# SPI_schematic.net
KiCad netlist of a schematic drawn in EAGLE
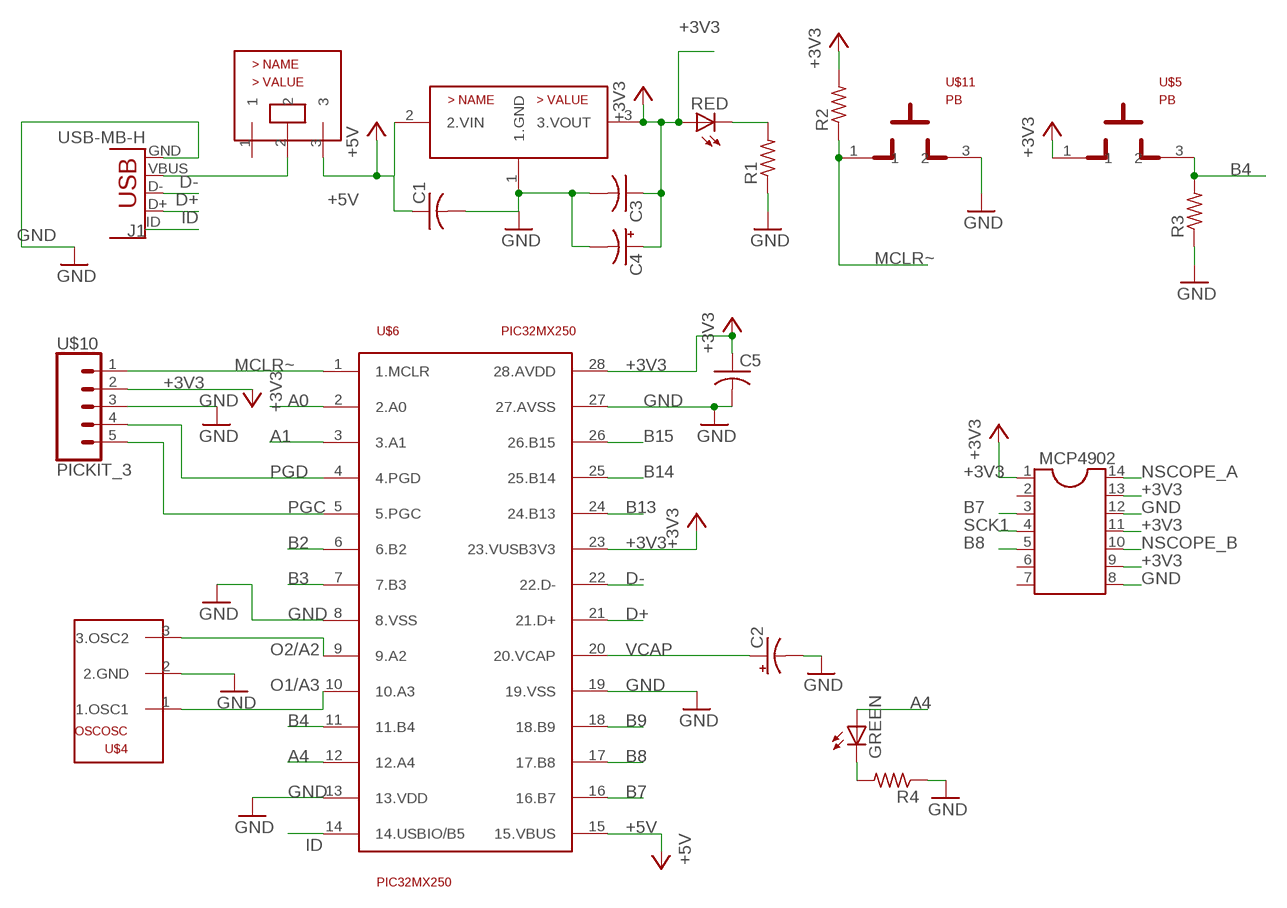
[diagram p0: schematic, sheet 1]

(export (version "E")
  (design (tool "Eeschema 10.0.6"))
  (components
    (comp (ref "C1")
      (value "C-US025-025X050")
      (footprint "eagle-import:C025-025X050")
      (libsource (lib "eagle-import") (part "C-US025-025X050"))
    )
    (comp (ref "C2")
      (value "CPOL-USB45181B")
      (footprint "eagle-import:B45181B")
      (libsource (lib "eagle-import") (part "CPOL-USB45181B"))
    )
    (comp (ref "C3")
      (value "C-US025-025X050")
      (footprint "eagle-import:C025-025X050")
      (libsource (lib "eagle-import") (part "C-US025-025X050"))
    )
    (comp (ref "C4")
      (value "CPOL-USB45181B")
      (footprint "eagle-import:B45181B")
      (libsource (lib "eagle-import") (part "CPOL-USB45181B"))
    )
    (comp (ref "C5")
      (value "C-US025-025X050")
      (footprint "eagle-import:C025-025X050")
      (libsource (lib "eagle-import") (part "C-US025-025X050"))
    )
    (comp (ref "GREEN")
      (value "LED3MM")
      (footprint "eagle-import:LED3MM")
      (libsource (lib "eagle-import") (part "LED3MM"))
    )
    (comp (ref "J1")
      (value "USB-MB-H")
      (footprint "eagle-import:USB-MB-H")
      (libsource (lib "eagle-import") (part "USB-MB-H"))
    )
    (comp (ref "MCP4902")
      (value "DIL14")
      (footprint "eagle-import:DIL14")
      (libsource (lib "eagle-import") (part "DIL14"))
    )
    (comp (ref "R1")
      (value "R-US_0204/7")
      (footprint "eagle-import:0204_7")
      (libsource (lib "eagle-import") (part "R-US_0204/7"))
    )
    (comp (ref "R2")
      (value "R-US_0204/7")
      (footprint "eagle-import:0204_7")
      (libsource (lib "eagle-import") (part "R-US_0204/7"))
    )
    (comp (ref "R3")
      (value "R-US_0204/7")
      (footprint "eagle-import:0204_7")
      (libsource (lib "eagle-import") (part "R-US_0204/7"))
    )
    (comp (ref "R4")
      (value "R-US_0204/7")
      (footprint "eagle-import:0204_7")
      (libsource (lib "eagle-import") (part "R-US_0204/7"))
    )
    (comp (ref "RED")
      (value "LED3MM")
      (footprint "eagle-import:LED3MM")
      (libsource (lib "eagle-import") (part "LED3MM"))
    )
    (comp (ref "U$4")
      (value "OSCOSC")
      (footprint "eagle-import:OSC")
      (libsource (lib "eagle-import") (part "OSCOSC"))
    )
    (comp (ref "U$5") (value "PB") (footprint "eagle-import:PB") (libsource (lib "eagle-import") (part "PB")))
    (comp (ref "U$6")
      (value "PIC32MX250")
      (footprint "eagle-import:DIL28-3")
      (libsource (lib "eagle-import") (part "PIC32MX250"))
    )
    (comp (ref "U$8")
      (value "SLIDE")
      (footprint "eagle-import:SLIDE")
      (libsource (lib "eagle-import") (part "SLIDE"))
    )
    (comp (ref "U$10")
      (value "PICKIT_3")
      (footprint "eagle-import:1X05")
      (libsource (lib "eagle-import") (part "PICKIT_3"))
    )
    (comp (ref "U$11")
      (value "PB")
      (footprint "eagle-import:PB")
      (libsource (lib "eagle-import") (part "PB"))
    )
    (comp (ref "_")
      (value "MCP1702")
      (footprint "eagle-import:TO92")
      (libsource (lib "eagle-import") (part "MCP1702"))
    )
  )
  (nets
    (net (code "1") (name "+3V3") (class "Default")
      (node (ref "C3") (pin "1") (pinfunction "1_1") (pintype "passive"))
      (node (ref "C4") (pin "+") (pinfunction "+_+") (pintype "passive"))
      (node (ref "C5") (pin "1") (pinfunction "1_1") (pintype "passive"))
      (node (ref "MCP4902") (pin "1") (pinfunction "1_1") (pintype "passive"))
      (node (ref "MCP4902") (pin "11") (pinfunction "11_11") (pintype "passive"))
      (node (ref "MCP4902") (pin "13") (pinfunction "13_13") (pintype "passive"))
      (node (ref "MCP4902") (pin "9") (pinfunction "9_9") (pintype "passive"))
      (node (ref "R2") (pin "2") (pinfunction "2_2") (pintype "passive"))
      (node (ref "RED") (pin "A") (pinfunction "A_A") (pintype "passive"))
      (node (ref "U$10") (pin "2") (pinfunction "2.VDD_2") (pintype "passive"))
      (node (ref "U$5") (pin "1") (pinfunction "1_1") (pintype "bidirectional"))
      (node (ref "U$6") (pin "23") (pinfunction "23.VUSB3V3_23") (pintype "bidirectional"))
      (node (ref "U$6") (pin "28") (pinfunction "28.AVDD_28") (pintype "bidirectional"))
      (node (ref "_") (pin "3") (pinfunction "3.VOUT_3") (pintype "bidirectional"))
    )
    (net (code "2") (name "+5V") (class "Default")
      (node (ref "C1") (pin "1") (pinfunction "1_1") (pintype "passive"))
      (node (ref "U$6") (pin "15") (pinfunction "15.VBUS_15") (pintype "bidirectional"))
      (node (ref "U$8") (pin "3") (pinfunction "3_3") (pintype "bidirectional"))
      (node (ref "_") (pin "2") (pinfunction "2.VIN_2") (pintype "bidirectional"))
    )
    (net (code "3") (name "/A0") (class "Default")
      (node (ref "U$6") (pin "2") (pinfunction "2.A0_2") (pintype "bidirectional"))
    )
    (net (code "4") (name "/A1") (class "Default")
      (node (ref "U$6") (pin "3") (pinfunction "3.A1_3") (pintype "bidirectional"))
    )
    (net (code "5") (name "/A4") (class "Default")
      (node (ref "GREEN") (pin "A") (pinfunction "A_A") (pintype "passive"))
      (node (ref "U$6") (pin "12") (pinfunction "12.A4_12") (pintype "bidirectional"))
    )
    (net (code "6") (name "/B2") (class "Default")
      (node (ref "U$6") (pin "6") (pinfunction "6.B2_6") (pintype "bidirectional"))
    )
    (net (code "7") (name "/B3") (class "Default")
      (node (ref "U$6") (pin "7") (pinfunction "7.B3_7") (pintype "bidirectional"))
    )
    (net (code "8") (name "/B4") (class "Default")
      (node (ref "R3") (pin "2") (pinfunction "2_2") (pintype "passive"))
      (node (ref "U$5") (pin "3") (pinfunction "2_3") (pintype "bidirectional"))
      (node (ref "U$6") (pin "11") (pinfunction "11.B4_11") (pintype "bidirectional"))
    )
    (net (code "9") (name "/B7") (class "Default")
      (node (ref "MCP4902") (pin "3") (pinfunction "3_3") (pintype "passive"))
      (node (ref "U$6") (pin "16") (pinfunction "16.B7_16") (pintype "bidirectional"))
    )
    (net (code "10") (name "/B8") (class "Default")
      (node (ref "MCP4902") (pin "5") (pinfunction "5_5") (pintype "passive"))
      (node (ref "U$6") (pin "17") (pinfunction "17.B8_17") (pintype "bidirectional"))
    )
    (net (code "11") (name "/B9") (class "Default")
      (node (ref "U$6") (pin "18") (pinfunction "18.B9_18") (pintype "bidirectional"))
    )
    (net (code "12") (name "/B13") (class "Default")
      (node (ref "U$6") (pin "24") (pinfunction "24.B13_24") (pintype "bidirectional"))
    )
    (net (code "13") (name "/B14") (class "Default")
      (node (ref "U$6") (pin "25") (pinfunction "25.B14_25") (pintype "bidirectional"))
    )
    (net (code "14") (name "/B15") (class "Default")
      (node (ref "U$6") (pin "26") (pinfunction "26.B15_26") (pintype "bidirectional"))
    )
    (net (code "15") (name "/D+") (class "Default")
      (node (ref "J1") (pin "D+") (pinfunction "D+_D+") (pintype "bidirectional"))
      (node (ref "U$6") (pin "21") (pinfunction "21.D+_21") (pintype "bidirectional"))
    )
    (net (code "16") (name "/D-") (class "Default")
      (node (ref "J1") (pin "D-") (pinfunction "D-_D-") (pintype "bidirectional"))
      (node (ref "U$6") (pin "22") (pinfunction "22.D-_22") (pintype "bidirectional"))
    )
    (net (code "17") (name "/ID") (class "Default")
      (node (ref "J1") (pin "ID") (pinfunction "ID_ID") (pintype "bidirectional"))
      (node (ref "U$6") (pin "14") (pinfunction "14.USBIO/B5_14") (pintype "bidirectional"))
    )
    (net (code "18") (name "/MCLR~{}") (class "Default")
      (node (ref "R2") (pin "1") (pinfunction "1_1") (pintype "passive"))
      (node (ref "U$10") (pin "1") (pinfunction "1.MCLR~{}_1") (pintype "passive"))
      (node (ref "U$11") (pin "1") (pinfunction "1_1") (pintype "bidirectional"))
      (node (ref "U$6") (pin "1") (pinfunction "1.MCLR_1") (pintype "bidirectional"))
    )
    (net (code "19") (name "/NSCOPE_A") (class "Default")
      (node (ref "MCP4902") (pin "14") (pinfunction "14_14") (pintype "passive"))
    )
    (net (code "20") (name "/NSCOPE_B") (class "Default")
      (node (ref "MCP4902") (pin "10") (pinfunction "10_10") (pintype "passive"))
    )
    (net (code "21") (name "/O1{slash}A3") (class "Default")
      (node (ref "U$4") (pin "1") (pinfunction "1.OSC1_1") (pintype "bidirectional"))
      (node (ref "U$6") (pin "10") (pinfunction "10.A3_10") (pintype "bidirectional"))
    )
    (net (code "22") (name "/O2{slash}A2") (class "Default")
      (node (ref "U$4") (pin "3") (pinfunction "3.OSC2_3") (pintype "bidirectional"))
      (node (ref "U$6") (pin "9") (pinfunction "9.A2_9") (pintype "bidirectional"))
    )
    (net (code "23") (name "/PGC") (class "Default")
      (node (ref "U$10") (pin "5") (pinfunction "5.PGC_5") (pintype "passive"))
      (node (ref "U$6") (pin "5") (pinfunction "5.PGC_5") (pintype "bidirectional"))
    )
    (net (code "24") (name "/PGD") (class "Default")
      (node (ref "U$10") (pin "4") (pinfunction "4.PGD_4") (pintype "passive"))
      (node (ref "U$6") (pin "4") (pinfunction "4.PGD_4") (pintype "bidirectional"))
    )
    (net (code "25") (name "/SCK1") (class "Default")
      (node (ref "MCP4902") (pin "4") (pinfunction "4_4") (pintype "passive"))
    )
    (net (code "26") (name "/VCAP") (class "Default")
      (node (ref "C2") (pin "+") (pinfunction "+_+") (pintype "passive"))
      (node (ref "U$6") (pin "20") (pinfunction "20.VCAP_20") (pintype "bidirectional"))
    )
    (net (code "27") (name "GND") (class "Default")
      (node (ref "C1") (pin "2") (pinfunction "2_2") (pintype "passive"))
      (node (ref "C2") (pin "-") (pinfunction "-_-") (pintype "passive"))
      (node (ref "C3") (pin "2") (pinfunction "2_2") (pintype "passive"))
      (node (ref "C4") (pin "-") (pinfunction "-_-") (pintype "passive"))
      (node (ref "C5") (pin "2") (pinfunction "2_2") (pintype "passive"))
      (node (ref "J1") (pin "GND") (pinfunction "GND_GND") (pintype "bidirectional"))
      (node (ref "MCP4902") (pin "12") (pinfunction "12_12") (pintype "passive"))
      (node (ref "MCP4902") (pin "8") (pinfunction "8_8") (pintype "passive"))
      (node (ref "R1") (pin "1") (pinfunction "1_1") (pintype "passive"))
      (node (ref "R3") (pin "1") (pinfunction "1_1") (pintype "passive"))
      (node (ref "R4") (pin "1") (pinfunction "1_1") (pintype "passive"))
      (node (ref "U$10") (pin "3") (pinfunction "3.VSS_3") (pintype "passive"))
      (node (ref "U$11") (pin "3") (pinfunction "2_3") (pintype "bidirectional"))
      (node (ref "U$4") (pin "2") (pinfunction "2.GND_2") (pintype "bidirectional"))
      (node (ref "U$6") (pin "13") (pinfunction "13.VDD_13") (pintype "bidirectional"))
      (node (ref "U$6") (pin "19") (pinfunction "19.VSS_19") (pintype "bidirectional"))
      (node (ref "U$6") (pin "27") (pinfunction "27.AVSS_27") (pintype "bidirectional"))
      (node (ref "U$6") (pin "8") (pinfunction "8.VSS_8") (pintype "bidirectional"))
      (node (ref "_") (pin "1") (pinfunction "1.GND_1") (pintype "bidirectional"))
    )
    (net (code "28") (name "Net-(GREEN-C)") (class "Default")
      (node (ref "GREEN") (pin "K") (pinfunction "C_K") (pintype "passive"))
      (node (ref "R4") (pin "2") (pinfunction "2_2") (pintype "passive"))
    )
    (net (code "29") (name "Net-(J1-PadVBUS)") (class "Default")
      (node (ref "J1") (pin "VBUS") (pinfunction "VBUS_VBUS") (pintype "bidirectional"))
      (node (ref "U$8") (pin "2") (pinfunction "2_2") (pintype "bidirectional"))
    )
    (net (code "30") (name "Net-(RED-C)") (class "Default")
      (node (ref "R1") (pin "2") (pinfunction "2_2") (pintype "passive"))
      (node (ref "RED") (pin "K") (pinfunction "C_K") (pintype "passive"))
    )
    (net (code "31") (name "unconnected-(MCP4902-Pad2)") (class "Default")
      (node (ref "MCP4902") (pin "2") (pinfunction "2_2") (pintype "passive"))
    )
    (net (code "32") (name "unconnected-(MCP4902-Pad6)") (class "Default")
      (node (ref "MCP4902") (pin "6") (pinfunction "6_6") (pintype "passive"))
    )
    (net (code "33") (name "unconnected-(MCP4902-Pad7)") (class "Default")
      (node (ref "MCP4902") (pin "7") (pinfunction "7_7") (pintype "passive"))
    )
    (net (code "34") (name "unconnected-(U$8-Pad1)") (class "Default")
      (node (ref "U$8") (pin "1") (pinfunction "1_1") (pintype "bidirectional"))
    )
  )
)
